# S7CAS-PLEIADES-CARTE-MERE_Pxx_FLASH_PHY_.net
KiCad netlist of a schematic drawn in Altium Designer
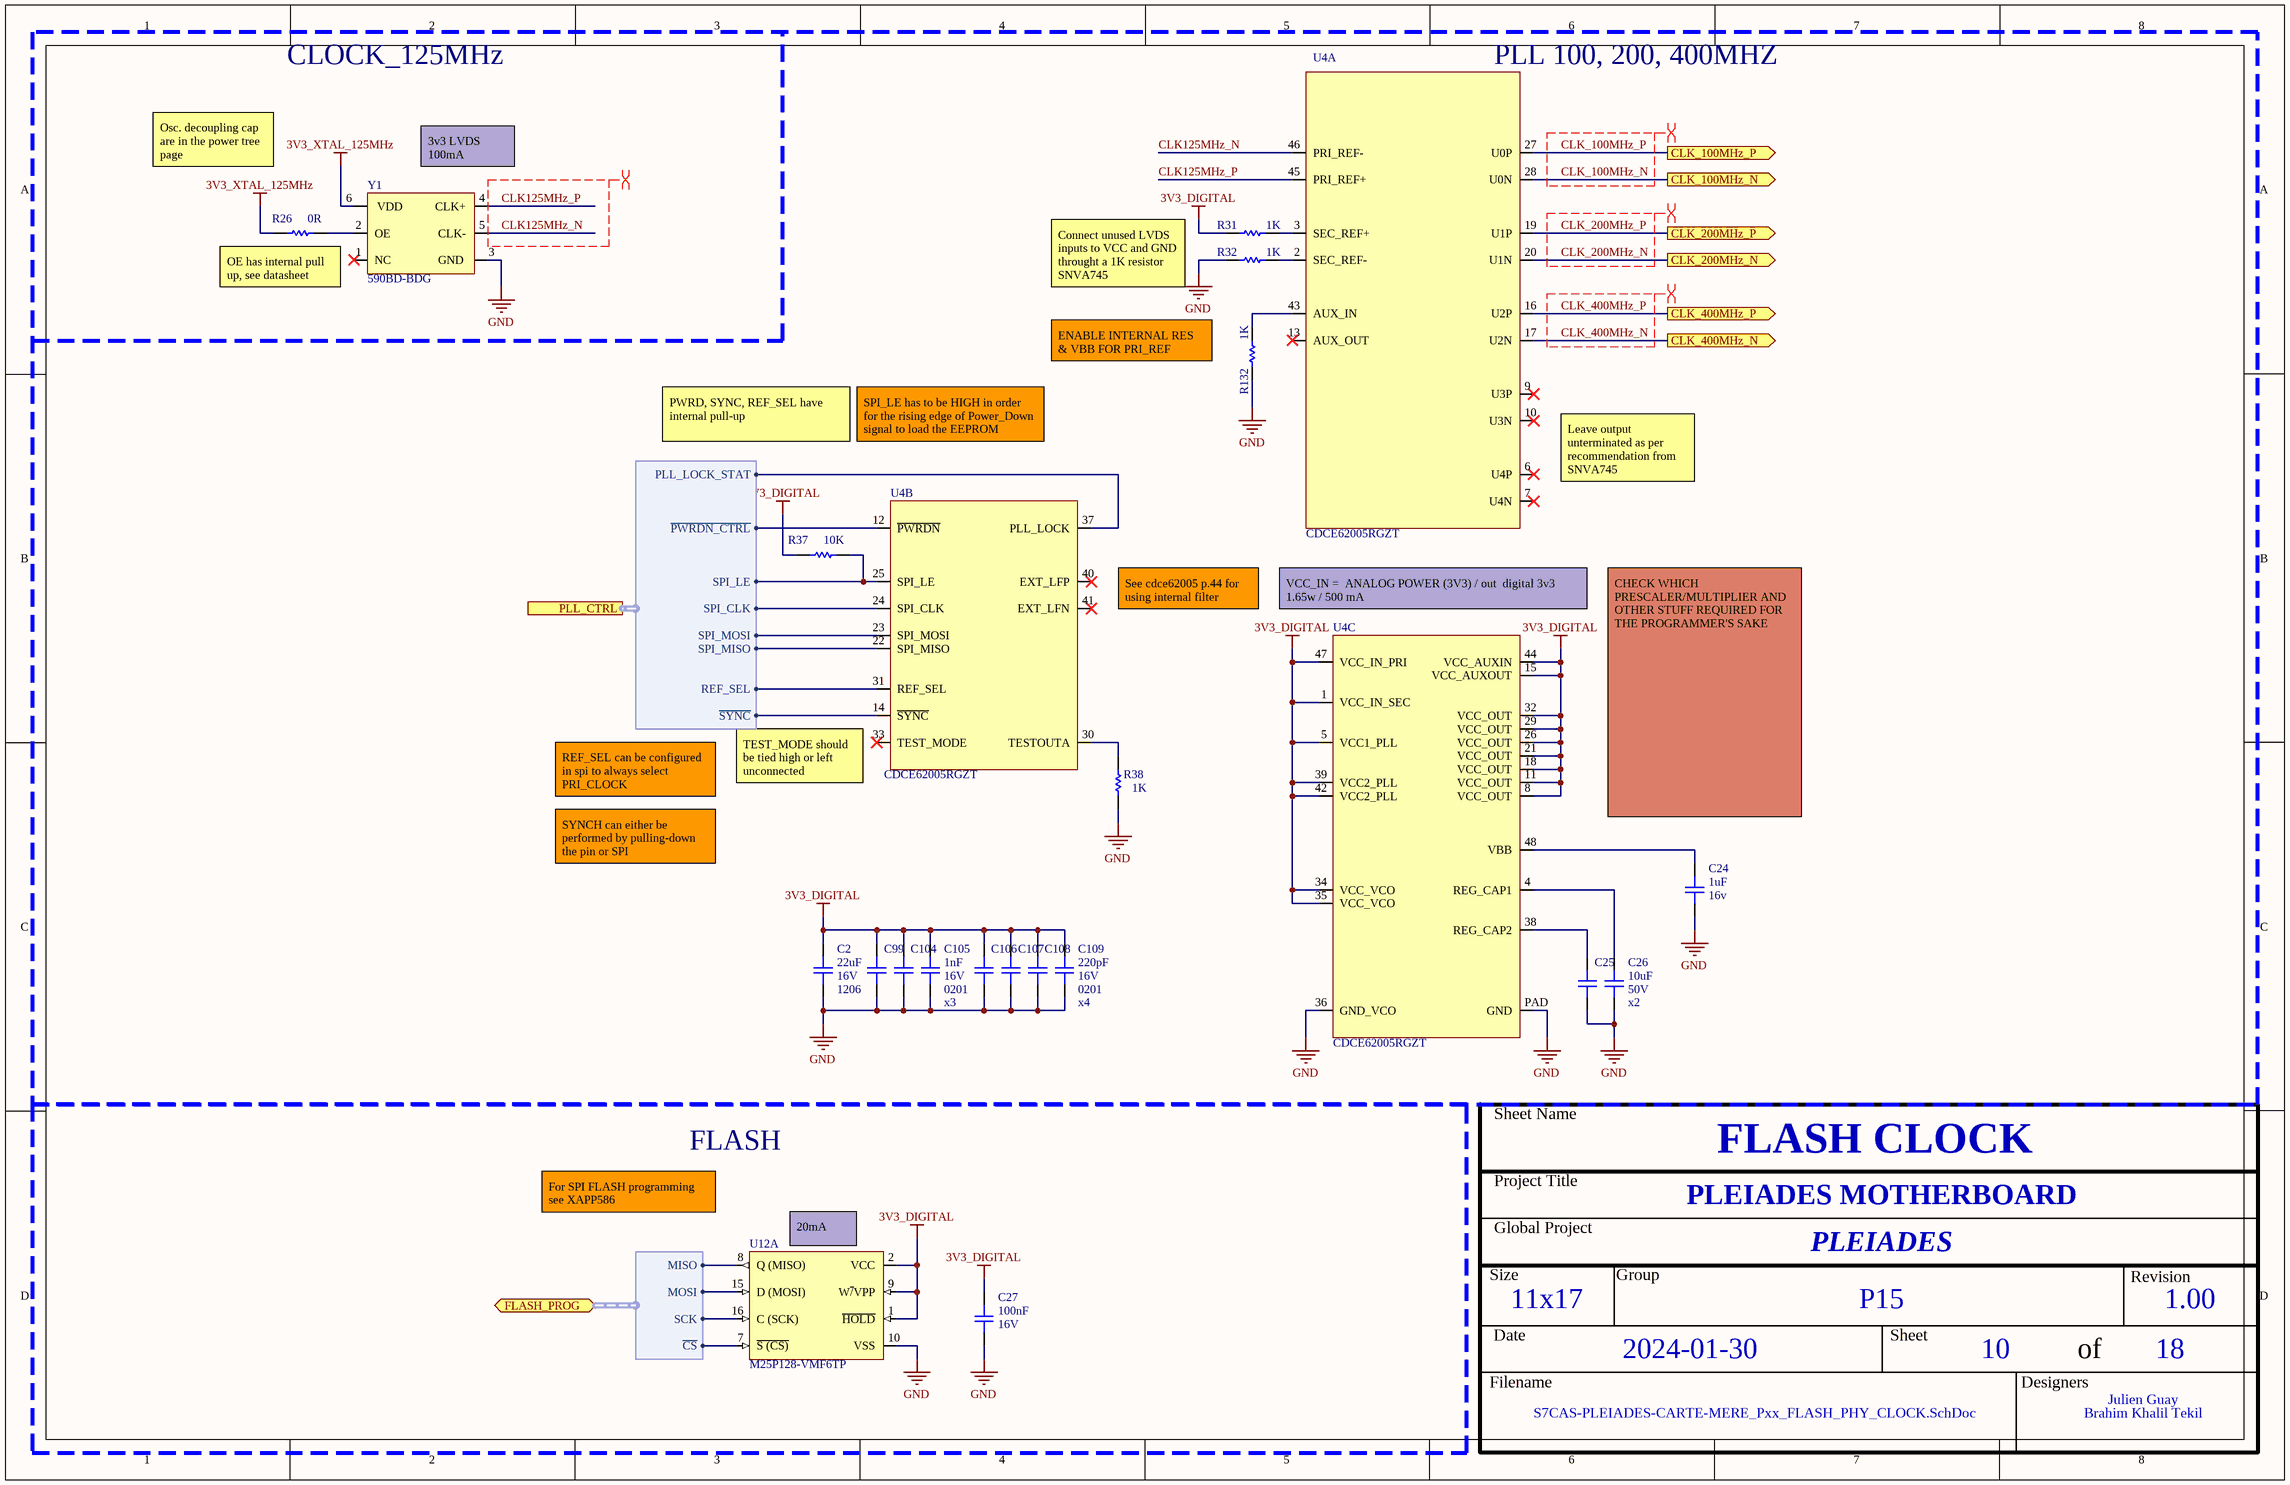
[diagram p0: S7CAS-PLEIADES-CARTE-MERE_Pxx_FLASH_PHY_CLOCK.SchDoc]

(export (version "E")
  (design (tool "Eeschema 10.0.6"))
  (components
    (comp (ref "C2")
      (value "22uF")
      (footprint "CAP_1206")
      (description "CAP - 1206")
      (fields
        (field (name "VOLTAGE") "16V")
        (field (name "PACKAGE") "1206")
        (field (name "CREATEDBY") "Jonathan Bouchard")
      )
      (libsource (lib "S7CAS_LIB2023") (part "CAP - 1206"))
    )
    (comp (ref "C24")
      (value "1uF")
      (footprint "CAP_0603")
      (description "CAP - 0603")
      (fields (field (name "VOLTAGE") "16v") (field (name "CREATEDBY") "Jonathan Bouchard"))
      (libsource (lib "S7CAS_LIB2023") (part "CAP - 0603"))
    )
    (comp (ref "C25")
      (value "CAP - 1206")
      (footprint "CAP_1206")
      (fields (field (name "VOLTAGE") "50V") (field (name "CREATEDBY") "Jonathan Bouchard"))
      (libsource (lib "S7CAS_LIB2023") (part "CAP - 1206"))
    )
    (comp (ref "C26")
      (value "10uF")
      (footprint "CAP_1206")
      (description "CAP - 1206")
      (fields (field (name "VOLTAGE") "50V") (field (name "CREATEDBY") "Jonathan Bouchard"))
      (libsource (lib "S7CAS_LIB2023") (part "CAP - 1206"))
    )
    (comp (ref "C27")
      (value "100nF")
      (footprint "CAP_0603")
      (description "CAP - 0603")
      (fields (field (name "VOLTAGE") "16V") (field (name "CREATEDBY") "Jonathan Bouchard"))
      (libsource (lib "S7CAS_LIB2023") (part "CAP - 0603"))
    )
    (comp (ref "C99")
      (value "CAP - 0201")
      (footprint "CAP_0201")
      (fields (field (name "VOLTAGE") "16V") (field (name "CREATEDBY") "Jonathan Bouchard"))
      (libsource (lib "S7CAS_LIB2023") (part "CAP - 0201"))
    )
    (comp (ref "C104")
      (value "CAP - 0201")
      (footprint "CAP_0201")
      (fields (field (name "VOLTAGE") "16V") (field (name "CREATEDBY") "Jonathan Bouchard"))
      (libsource (lib "S7CAS_LIB2023") (part "CAP - 0201"))
    )
    (comp (ref "C105")
      (value "1nF")
      (footprint "CAP_0201")
      (description "CAP - 0201")
      (fields
        (field (name "VOLTAGE") "16V")
        (field (name "PACKAGE") "0201")
        (field (name "CREATEDBY") "Jonathan Bouchard")
      )
      (libsource (lib "S7CAS_LIB2023") (part "CAP - 0201"))
    )
    (comp (ref "C106")
      (value "CAP - 0201")
      (footprint "CAP_0201")
      (fields (field (name "VOLTAGE") "16V") (field (name "CREATEDBY") "Jonathan Bouchard"))
      (libsource (lib "S7CAS_LIB2023") (part "CAP - 0201"))
    )
    (comp (ref "C107")
      (value "CAP - 0201")
      (footprint "CAP_0201")
      (fields (field (name "VOLTAGE") "16V") (field (name "CREATEDBY") "Jonathan Bouchard"))
      (libsource (lib "S7CAS_LIB2023") (part "CAP - 0201"))
    )
    (comp (ref "C108")
      (value "CAP - 0201")
      (footprint "CAP_0201")
      (fields (field (name "VOLTAGE") "16V") (field (name "CREATEDBY") "Jonathan Bouchard"))
      (libsource (lib "S7CAS_LIB2023") (part "CAP - 0201"))
    )
    (comp (ref "C109")
      (value "220pF")
      (footprint "CAP_0201")
      (description "CAP - 0201")
      (fields
        (field (name "VOLTAGE") "16V")
        (field (name "PACKAGE") "0201")
        (field (name "CREATEDBY") "Jonathan Bouchard")
      )
      (libsource (lib "S7CAS_LIB2023") (part "CAP - 0201"))
    )
    (comp (ref "R26")
      (value "0R")
      (footprint "RES_0603")
      (description "RES - 0603")
      (fields (field (name "CREATEDBY") "Jonathan Bouchard"))
      (libsource (lib "S7CAS_LIB2023") (part "RES - 0603"))
    )
    (comp (ref "R31")
      (value "1K")
      (footprint "RES_0603")
      (description "RES - 0603")
      (fields (field (name "CREATEDBY") "Jonathan Bouchard"))
      (libsource (lib "S7CAS_LIB2023") (part "RES - 0603"))
    )
    (comp (ref "R32")
      (value "1K")
      (footprint "RES_0603")
      (description "RES - 0603")
      (fields (field (name "CREATEDBY") "Jonathan Bouchard"))
      (libsource (lib "S7CAS_LIB2023") (part "RES - 0603"))
    )
    (comp (ref "R37")
      (value "10K")
      (footprint "RES_0603")
      (description "RES - 0603")
      (fields (field (name "CREATEDBY") "Jonathan Bouchard"))
      (libsource (lib "S7CAS_LIB2023") (part "RES - 0603"))
    )
    (comp (ref "R38")
      (value "1K")
      (footprint "RES_0603")
      (description "RES - 0603")
      (fields (field (name "CREATEDBY") "Jonathan Bouchard"))
      (libsource (lib "S7CAS_LIB2023") (part "RES - 0603"))
    )
    (comp (ref "R132")
      (value "1K")
      (footprint "RES_0603")
      (description "RES - 0603")
      (fields (field (name "CREATEDBY") "Jonathan Bouchard"))
      (libsource (lib "S7CAS_LIB2023") (part "RES - 0603"))
    )
    (comp (ref "U4")
      (value "CDCE62005RGZT")
      (footprint "TIM_CDCE62005RGZT")
      (description "TIM - CLK SYNTH JITTER CLEANER 3:5 - QFN-48")
      (fields
        (field (name "VOLTAGE") "3 V ~ 3.6 V")
        (field (name "MFG") "Texas Instruments")
        (field (name "CREATEDBY") "Jonathan Bouchard")
      )
      (libsource (lib "S7CAS_LIB2023") (part "TIM_CDCE62005RGZT"))
    )
    (comp (ref "U12")
      (value "M25P128-VMF6TP")
      (footprint "FLASH - M25P128-VMF6TP")
      (description "128-Mbit, low-voltage, serial flash memory\r\nwith 54-MHz SPI bus interface")
      (libsource (lib "S7CAS_LIB2023") (part "FLASH  - M25P128-VMF6TP"))
    )
    (comp (ref "Y1")
      (value "590BD-BDG")
      (footprint "OSC_590BD-BDG")
      (description "TIM - OSC PROG 125MHz ~ 214.999MHz LVDS 3.3V 7PPM EN/DS - 6-SMD")
      (fields
        (field (name "CREATEDBY/DATE") "from 590BD-CDG")
        (field (name "VERIFIEDBY") "Caroline Paulin / 3/10/2019")
      )
      (libsource (lib "S7CAS_LIB2023") (part "OSC_590BD-BDG"))
    )
  )
  (nets
    (net (code "3") (name "/CLK125MHz_N") (class "Default")
      (node (ref "U4") (pin "46") (pinfunction "PRI_REF-_46") (pintype "passive"))
      (node (ref "Y1") (pin "5") (pinfunction "CLK-_5") (pintype "passive"))
    )
    (net (code "4") (name "/CLK125MHz_P") (class "Default")
      (node (ref "U4") (pin "45") (pinfunction "PRI_REF+_45") (pintype "passive"))
      (node (ref "Y1") (pin "4") (pinfunction "CLK+_4") (pintype "passive"))
    )
    (net (code "5") (name "/CLK_100MHz_N") (class "Default")
      (node (ref "U4") (pin "28") (pinfunction "U0N_28") (pintype "passive"))
    )
    (net (code "6") (name "/CLK_100MHz_P") (class "Default")
      (node (ref "U4") (pin "27") (pinfunction "U0P_27") (pintype "passive"))
    )
    (net (code "7") (name "/CLK_200MHz_N") (class "Default")
      (node (ref "U4") (pin "20") (pinfunction "U1N_20") (pintype "passive"))
    )
    (net (code "8") (name "/CLK_200MHz_P") (class "Default")
      (node (ref "U4") (pin "19") (pinfunction "U1P_19") (pintype "passive"))
    )
    (net (code "9") (name "/CLK_400MHz_N") (class "Default")
      (node (ref "U4") (pin "17") (pinfunction "U2N_17") (pintype "passive"))
    )
    (net (code "10") (name "/CLK_400MHz_P") (class "Default")
      (node (ref "U4") (pin "16") (pinfunction "U2P_16") (pintype "passive"))
    )
    (net (code "11") (name "/MISO") (class "Default")
      (node (ref "U12") (pin "8") (pinfunction "Q_(MISO)_8") (pintype "output"))
    )
    (net (code "12") (name "/MOSI") (class "Default")
      (node (ref "U12") (pin "15") (pinfunction "D_(MOSI)_15") (pintype "input"))
    )
    (net (code "13") (name "/PLL_LOCK_STAT") (class "Default")
      (node (ref "U4") (pin "37") (pinfunction "PLL_LOCK_37") (pintype "passive"))
    )
    (net (code "14") (name "/REF_SEL") (class "Default")
      (node (ref "U4") (pin "31") (pinfunction "REF_SEL_31") (pintype "passive"))
    )
    (net (code "15") (name "/SCK") (class "Default")
      (node (ref "U12") (pin "16") (pinfunction "C_(SCK)_16") (pintype "input"))
    )
    (net (code "16") (name "/SPI_CLK") (class "Default")
      (node (ref "U4") (pin "24") (pinfunction "SPI_CLK_24") (pintype "passive"))
    )
    (net (code "17") (name "/SPI_LE") (class "Default")
      (node (ref "R37") (pin "1") (pinfunction "1_1") (pintype "passive"))
      (node (ref "U4") (pin "25") (pinfunction "SPI_LE_25") (pintype "passive"))
    )
    (net (code "18") (name "/SPI_MISO") (class "Default")
      (node (ref "U4") (pin "22") (pinfunction "SPI_MISO_22") (pintype "passive"))
    )
    (net (code "19") (name "/SPI_MOSI") (class "Default")
      (node (ref "U4") (pin "23") (pinfunction "SPI_MOSI_23") (pintype "passive"))
    )
    (net (code "22") (name "/~{CS}") (class "Default")
      (node (ref "U12") (pin "7") (pinfunction "S_(CS)_7") (pintype "input"))
    )
    (net (code "23") (name "/~{PWRDN_CTRL}") (class "Default")
      (node (ref "U4") (pin "12") (pinfunction "~{PWRDN}_12") (pintype "passive"))
    )
    (net (code "24") (name "/~{SYNC}") (class "Default")
      (node (ref "U4") (pin "14") (pinfunction "~{SYNC}_14") (pintype "passive"))
    )
    (net (code "25") (name "3V3_DIGITAL") (class "Default")
      (node (ref "C104") (pin "2") (pinfunction "2_2") (pintype "passive"))
      (node (ref "C105") (pin "2") (pinfunction "2_2") (pintype "passive"))
      (node (ref "C106") (pin "2") (pinfunction "2_2") (pintype "passive"))
      (node (ref "C107") (pin "2") (pinfunction "2_2") (pintype "passive"))
      (node (ref "C108") (pin "2") (pinfunction "2_2") (pintype "passive"))
      (node (ref "C109") (pin "2") (pinfunction "2_2") (pintype "passive"))
      (node (ref "C2") (pin "2") (pinfunction "2_2") (pintype "passive"))
      (node (ref "C27") (pin "2") (pinfunction "2_2") (pintype "passive"))
      (node (ref "C99") (pin "2") (pinfunction "2_2") (pintype "passive"))
      (node (ref "R31") (pin "2") (pinfunction "2_2") (pintype "passive"))
      (node (ref "R37") (pin "2") (pinfunction "2_2") (pintype "passive"))
      (node (ref "U12") (pin "1") (pinfunction "HOLD_1") (pintype "input"))
      (node (ref "U12") (pin "2") (pinfunction "VCC_2") (pintype "power_in"))
      (node (ref "U12") (pin "9") (pinfunction "W~{/}VPP_9") (pintype "input"))
      (node (ref "U4") (pin "1") (pinfunction "VCC_IN_SEC_1") (pintype "passive"))
      (node (ref "U4") (pin "11") (pinfunction "VCC_OUT_11") (pintype "passive"))
      (node (ref "U4") (pin "15") (pinfunction "VCC_AUXOUT_15") (pintype "passive"))
      (node (ref "U4") (pin "18") (pinfunction "VCC_OUT_18") (pintype "passive"))
      (node (ref "U4") (pin "21") (pinfunction "VCC_OUT_21") (pintype "passive"))
      (node (ref "U4") (pin "26") (pinfunction "VCC_OUT_26") (pintype "passive"))
      (node (ref "U4") (pin "29") (pinfunction "VCC_OUT_29") (pintype "passive"))
      (node (ref "U4") (pin "32") (pinfunction "VCC_OUT_32") (pintype "passive"))
      (node (ref "U4") (pin "34") (pinfunction "VCC_VCO_34") (pintype "passive"))
      (node (ref "U4") (pin "35") (pinfunction "VCC_VCO_35") (pintype "passive"))
      (node (ref "U4") (pin "39") (pinfunction "VCC2_PLL_39") (pintype "passive"))
      (node (ref "U4") (pin "42") (pinfunction "VCC2_PLL_42") (pintype "passive"))
      (node (ref "U4") (pin "44") (pinfunction "VCC_AUXIN_44") (pintype "passive"))
      (node (ref "U4") (pin "47") (pinfunction "VCC_IN_PRI_47") (pintype "passive"))
      (node (ref "U4") (pin "5") (pinfunction "VCC1_PLL_5") (pintype "passive"))
      (node (ref "U4") (pin "8") (pinfunction "VCC_OUT_8") (pintype "passive"))
    )
    (net (code "26") (name "3V3_XTAL_125MHz") (class "Default")
      (node (ref "R26") (pin "2") (pinfunction "2_2") (pintype "passive"))
      (node (ref "Y1") (pin "6") (pinfunction "VDD_6") (pintype "passive"))
    )
    (net (code "27") (name "GND") (class "Default")
      (node (ref "C104") (pin "1") (pinfunction "1_1") (pintype "passive"))
      (node (ref "C105") (pin "1") (pinfunction "1_1") (pintype "passive"))
      (node (ref "C106") (pin "1") (pinfunction "1_1") (pintype "passive"))
      (node (ref "C107") (pin "1") (pinfunction "1_1") (pintype "passive"))
      (node (ref "C108") (pin "1") (pinfunction "1_1") (pintype "passive"))
      (node (ref "C109") (pin "1") (pinfunction "1_1") (pintype "passive"))
      (node (ref "C2") (pin "1") (pinfunction "1_1") (pintype "passive"))
      (node (ref "C24") (pin "1") (pinfunction "1_1") (pintype "passive"))
      (node (ref "C25") (pin "1") (pinfunction "1_1") (pintype "passive"))
      (node (ref "C26") (pin "1") (pinfunction "1_1") (pintype "passive"))
      (node (ref "C27") (pin "1") (pinfunction "1_1") (pintype "passive"))
      (node (ref "C99") (pin "1") (pinfunction "1_1") (pintype "passive"))
      (node (ref "R132") (pin "2") (pinfunction "2_2") (pintype "passive"))
      (node (ref "R32") (pin "2") (pinfunction "2_2") (pintype "passive"))
      (node (ref "R38") (pin "1") (pinfunction "1_1") (pintype "passive"))
      (node (ref "U12") (pin "10") (pinfunction "VSS_10") (pintype "power_in"))
      (node (ref "U4") (pin "36") (pinfunction "GND_VCO_36") (pintype "passive"))
      (node (ref "U4") (pin "PAD") (pinfunction "GND_PAD") (pintype "passive"))
      (node (ref "Y1") (pin "3") (pinfunction "GND_3") (pintype "passive"))
    )
    (net (code "28") (name "Net-(U4A-AUX_IN)") (class "Default")
      (node (ref "R132") (pin "1") (pinfunction "1_1") (pintype "passive"))
      (node (ref "U4") (pin "43") (pinfunction "AUX_IN_43") (pintype "passive"))
    )
    (net (code "29") (name "Net-(U4A-SEC_REF+)") (class "Default")
      (node (ref "R31") (pin "1") (pinfunction "1_1") (pintype "passive"))
      (node (ref "U4") (pin "3") (pinfunction "SEC_REF+_3") (pintype "passive"))
    )
    (net (code "30") (name "Net-(U4A-SEC_REF-)") (class "Default")
      (node (ref "R32") (pin "1") (pinfunction "1_1") (pintype "passive"))
      (node (ref "U4") (pin "2") (pinfunction "SEC_REF-_2") (pintype "passive"))
    )
    (net (code "31") (name "Net-(U4B-TESTOUTA)") (class "Default")
      (node (ref "R38") (pin "2") (pinfunction "2_2") (pintype "passive"))
      (node (ref "U4") (pin "30") (pinfunction "TESTOUTA_30") (pintype "passive"))
    )
    (net (code "32") (name "Net-(U4C-REG_CAP1)") (class "Default")
      (node (ref "C26") (pin "2") (pinfunction "2_2") (pintype "passive"))
      (node (ref "U4") (pin "4") (pinfunction "REG_CAP1_4") (pintype "passive"))
    )
    (net (code "33") (name "Net-(U4C-REG_CAP2)") (class "Default")
      (node (ref "C25") (pin "2") (pinfunction "2_2") (pintype "passive"))
      (node (ref "U4") (pin "38") (pinfunction "REG_CAP2_38") (pintype "passive"))
    )
    (net (code "34") (name "Net-(U4C-VBB)") (class "Default")
      (node (ref "C24") (pin "2") (pinfunction "2_2") (pintype "passive"))
      (node (ref "U4") (pin "48") (pinfunction "VBB_48") (pintype "passive"))
    )
    (net (code "35") (name "Net-(Y1-OE)") (class "Default")
      (node (ref "R26") (pin "1") (pinfunction "1_1") (pintype "passive"))
      (node (ref "Y1") (pin "2") (pinfunction "OE_2") (pintype "passive"))
    )
    (net (code "36") (name "unconnected-(U4A-AUX_OUT-Pad13)") (class "Default")
      (node (ref "U4") (pin "13") (pinfunction "AUX_OUT_13") (pintype "passive+no_connect"))
    )
    (net (code "37") (name "unconnected-(U4A-U3N-Pad10)") (class "Default")
      (node (ref "U4") (pin "10") (pinfunction "U3N_10") (pintype "passive+no_connect"))
    )
    (net (code "38") (name "unconnected-(U4A-U3P-Pad9)") (class "Default")
      (node (ref "U4") (pin "9") (pinfunction "U3P_9") (pintype "passive+no_connect"))
    )
    (net (code "39") (name "unconnected-(U4A-U4N-Pad7)") (class "Default")
      (node (ref "U4") (pin "7") (pinfunction "U4N_7") (pintype "passive+no_connect"))
    )
    (net (code "40") (name "unconnected-(U4A-U4P-Pad6)") (class "Default")
      (node (ref "U4") (pin "6") (pinfunction "U4P_6") (pintype "passive+no_connect"))
    )
    (net (code "41") (name "unconnected-(U4B-EXT_LFN-Pad41)") (class "Default")
      (node (ref "U4") (pin "41") (pinfunction "EXT_LFN_41") (pintype "passive+no_connect"))
    )
    (net (code "42") (name "unconnected-(U4B-EXT_LFP-Pad40)") (class "Default")
      (node (ref "U4") (pin "40") (pinfunction "EXT_LFP_40") (pintype "passive+no_connect"))
    )
    (net (code "43") (name "unconnected-(U4B-TEST_MODE-Pad33)") (class "Default")
      (node (ref "U4") (pin "33") (pinfunction "TEST_MODE_33") (pintype "passive+no_connect"))
    )
    (net (code "44") (name "unconnected-(Y1-NC-Pad1)") (class "Default")
      (node (ref "Y1") (pin "1") (pinfunction "NC_1") (pintype "passive+no_connect"))
    )
  )
)
